# 566b4b7e-ffb1-47f2-8e62-ae72dd2330f2.net
KiCad netlist of a schematic drawn in EasyEDA
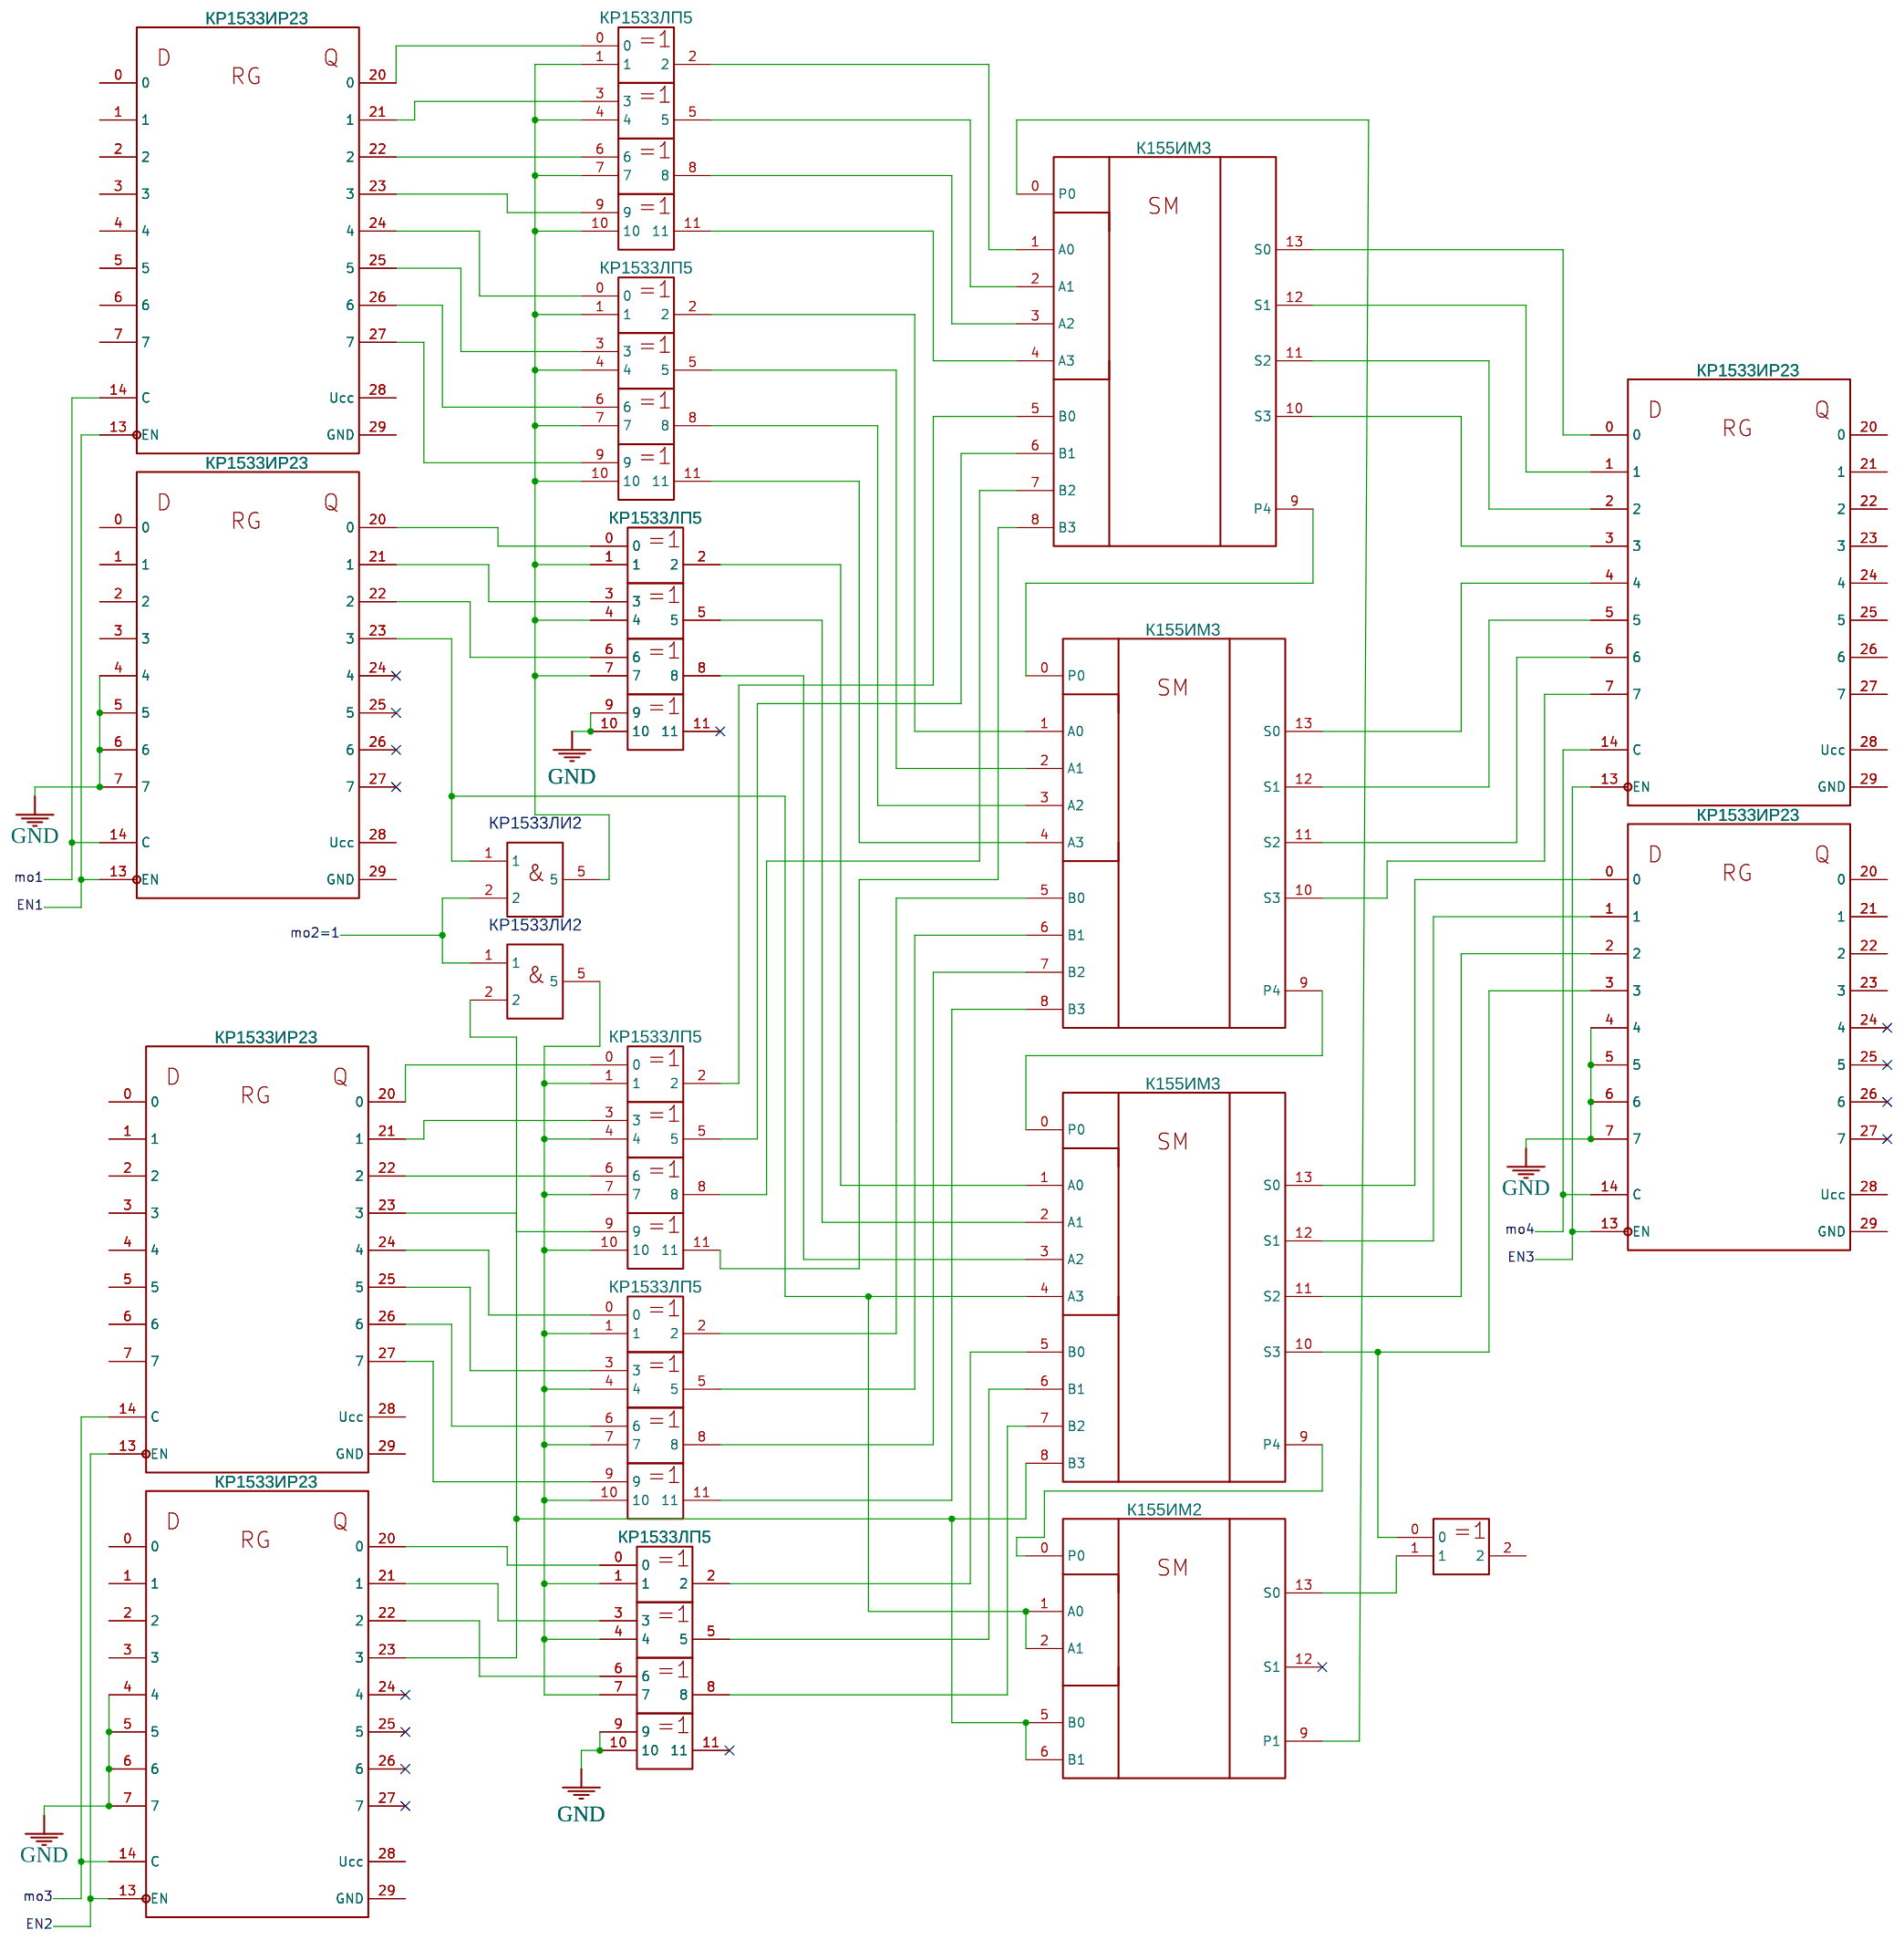
[diagram p0: schematic sheet]

(export (version "E")
  (design (tool "Eeschema 10.0.6"))
  (components
    (comp (ref "U1") (value "КР1533ИР23") (libsource (lib "") (part "regist_8")))
    (comp (ref "U2") (value "К155ИМ3") (libsource (lib "") (part "SM_1")))
    (comp (ref "U3") (value "and_or") (libsource (lib "") (part "and_or")))
    (comp (ref "U4") (value "КР1533ЛП5") (libsource (lib "") (part "4_xor")))
    (comp (ref "U5") (value "КР1533ЛП5") (libsource (lib "") (part "4_xor")))
    (comp (ref "U6") (value "КР1533ЛП5") (libsource (lib "") (part "4_xor")))
    (comp (ref "U7") (value "КР1533ИР23") (libsource (lib "") (part "regist_8")))
    (comp (ref "U8") (value "К155ИМ3") (libsource (lib "") (part "SM_1")))
    (comp (ref "U9") (value "КР1533ИР23") (libsource (lib "") (part "regist_8")))
    (comp (ref "U10") (value "КР1533ИР23") (libsource (lib "") (part "regist_8")))
    (comp (ref "U11") (value "КР1533ЛП5") (libsource (lib "") (part "4_xor")))
    (comp (ref "U12") (value "КР1533ЛП5") (libsource (lib "") (part "4_xor")))
    (comp (ref "U13") (value "КР1533ЛП5") (libsource (lib "") (part "4_xor")))
    (comp (ref "U14") (value "and_or") (libsource (lib "") (part "and_or")))
    (comp (ref "U15") (value "К155ИМ3") (libsource (lib "") (part "SM_1")))
    (comp (ref "U16") (value "КР1533ИР23") (libsource (lib "") (part "regist_8")))
    (comp (ref "U17") (value "КР1533ИР23") (libsource (lib "") (part "regist_8")))
    (comp (ref "U18") (value "К155ИМ2") (libsource (lib "") (part "SM")))
    (comp (ref "U19") (value "4_xor") (libsource (lib "") (part "4_xor_1")))
  )
  (nets
    (net (code "1") (name "/EN1") (class "Default")
      (node (ref "U1") (pin "13") (pinfunction "EN_13") (pintype "unspecified"))
      (node (ref "U7") (pin "13") (pinfunction "EN_13") (pintype "unspecified"))
    )
    (net (code "2") (name "/EN2") (class "Default")
      (node (ref "U10") (pin "13") (pinfunction "EN_13") (pintype "unspecified"))
      (node (ref "U9") (pin "13") (pinfunction "EN_13") (pintype "unspecified"))
    )
    (net (code "3") (name "/EN3") (class "Default")
      (node (ref "U16") (pin "13") (pinfunction "EN_13") (pintype "unspecified"))
      (node (ref "U17") (pin "13") (pinfunction "EN_13") (pintype "unspecified"))
    )
    (net (code "4") (name "/mo1") (class "Default")
      (node (ref "U1") (pin "14") (pinfunction "C_14") (pintype "unspecified"))
      (node (ref "U7") (pin "14") (pinfunction "C_14") (pintype "unspecified"))
    )
    (net (code "5") (name "/mo2=1") (class "Default")
      (node (ref "U14") (pin "1") (pinfunction "1_1") (pintype "unspecified"))
      (node (ref "U3") (pin "2") (pinfunction "2_2") (pintype "unspecified"))
    )
    (net (code "6") (name "/mo3") (class "Default")
      (node (ref "U10") (pin "14") (pinfunction "C_14") (pintype "unspecified"))
      (node (ref "U9") (pin "14") (pinfunction "C_14") (pintype "unspecified"))
    )
    (net (code "7") (name "/mo4") (class "Default")
      (node (ref "U16") (pin "14") (pinfunction "C_14") (pintype "unspecified"))
      (node (ref "U17") (pin "14") (pinfunction "C_14") (pintype "unspecified"))
    )
    (net (code "8") (name "GND") (class "Default")
      (node (ref "U1") (pin "4") (pinfunction "4_4") (pintype "unspecified"))
      (node (ref "U1") (pin "5") (pinfunction "5_5") (pintype "unspecified"))
      (node (ref "U1") (pin "6") (pinfunction "6_6") (pintype "unspecified"))
      (node (ref "U1") (pin "7") (pinfunction "7_7") (pintype "unspecified"))
      (node (ref "U11") (pin "10") (pinfunction "10_10") (pintype "unspecified"))
      (node (ref "U11") (pin "9") (pinfunction "9_9") (pintype "unspecified"))
      (node (ref "U16") (pin "4") (pinfunction "4_4") (pintype "unspecified"))
      (node (ref "U16") (pin "5") (pinfunction "5_5") (pintype "unspecified"))
      (node (ref "U16") (pin "6") (pinfunction "6_6") (pintype "unspecified"))
      (node (ref "U16") (pin "7") (pinfunction "7_7") (pintype "unspecified"))
      (node (ref "U6") (pin "10") (pinfunction "10_10") (pintype "unspecified"))
      (node (ref "U6") (pin "9") (pinfunction "9_9") (pintype "unspecified"))
      (node (ref "U9") (pin "4") (pinfunction "4_4") (pintype "unspecified"))
      (node (ref "U9") (pin "5") (pinfunction "5_5") (pintype "unspecified"))
      (node (ref "U9") (pin "6") (pinfunction "6_6") (pintype "unspecified"))
      (node (ref "U9") (pin "7") (pinfunction "7_7") (pintype "unspecified"))
    )
    (net (code "9") (name "Net-(U1-0-Pad20)") (class "Default")
      (node (ref "U1") (pin "20") (pinfunction "0_20") (pintype "unspecified"))
      (node (ref "U6") (pin "0") (pinfunction "0_0") (pintype "unspecified"))
    )
    (net (code "10") (name "Net-(U1-1-Pad21)") (class "Default")
      (node (ref "U1") (pin "21") (pinfunction "1_21") (pintype "unspecified"))
      (node (ref "U6") (pin "3") (pinfunction "3_3") (pintype "unspecified"))
    )
    (net (code "11") (name "Net-(U1-2-Pad22)") (class "Default")
      (node (ref "U1") (pin "22") (pinfunction "2_22") (pintype "unspecified"))
      (node (ref "U6") (pin "6") (pinfunction "6_6") (pintype "unspecified"))
    )
    (net (code "12") (name "Net-(U2-A0)") (class "Default")
      (node (ref "U2") (pin "1") (pinfunction "A0_1") (pintype "unspecified"))
      (node (ref "U4") (pin "2") (pinfunction "2_2") (pintype "unspecified"))
    )
    (net (code "13") (name "Net-(U2-A1)") (class "Default")
      (node (ref "U2") (pin "2") (pinfunction "A1_2") (pintype "unspecified"))
      (node (ref "U4") (pin "5") (pinfunction "5_5") (pintype "unspecified"))
    )
    (net (code "14") (name "Net-(U2-A2)") (class "Default")
      (node (ref "U2") (pin "3") (pinfunction "A2_3") (pintype "unspecified"))
      (node (ref "U4") (pin "8") (pinfunction "8_8") (pintype "unspecified"))
    )
    (net (code "15") (name "Net-(U2-A3)") (class "Default")
      (node (ref "U2") (pin "4") (pinfunction "A3_4") (pintype "unspecified"))
      (node (ref "U4") (pin "11") (pinfunction "11_11") (pintype "unspecified"))
    )
    (net (code "16") (name "Net-(U2-B0)") (class "Default")
      (node (ref "U13") (pin "2") (pinfunction "2_2") (pintype "unspecified"))
      (node (ref "U2") (pin "5") (pinfunction "B0_5") (pintype "unspecified"))
    )
    (net (code "17") (name "Net-(U2-B1)") (class "Default")
      (node (ref "U13") (pin "5") (pinfunction "5_5") (pintype "unspecified"))
      (node (ref "U2") (pin "6") (pinfunction "B1_6") (pintype "unspecified"))
    )
    (net (code "18") (name "Net-(U2-B2)") (class "Default")
      (node (ref "U13") (pin "8") (pinfunction "8_8") (pintype "unspecified"))
      (node (ref "U2") (pin "7") (pinfunction "B2_7") (pintype "unspecified"))
    )
    (net (code "19") (name "Net-(U2-B3)") (class "Default")
      (node (ref "U13") (pin "11") (pinfunction "11_11") (pintype "unspecified"))
      (node (ref "U2") (pin "8") (pinfunction "B3_8") (pintype "unspecified"))
    )
    (net (code "20") (name "Net-(U2-P4)") (class "Default")
      (node (ref "U2") (pin "9") (pinfunction "P4_9") (pintype "unspecified"))
      (node (ref "U8") (pin "0") (pinfunction "P0_0") (pintype "unspecified"))
    )
    (net (code "21") (name "Net-(U2-S0)") (class "Default")
      (node (ref "U17") (pin "0") (pinfunction "0_0") (pintype "unspecified"))
      (node (ref "U2") (pin "13") (pinfunction "S0_13") (pintype "unspecified"))
    )
    (net (code "22") (name "Net-(U2-S1)") (class "Default")
      (node (ref "U17") (pin "1") (pinfunction "1_1") (pintype "unspecified"))
      (node (ref "U2") (pin "12") (pinfunction "S1_12") (pintype "unspecified"))
    )
    (net (code "23") (name "Net-(U2-S2)") (class "Default")
      (node (ref "U17") (pin "2") (pinfunction "2_2") (pintype "unspecified"))
      (node (ref "U2") (pin "11") (pinfunction "S2_11") (pintype "unspecified"))
    )
    (net (code "24") (name "Net-(U2-S3)") (class "Default")
      (node (ref "U17") (pin "3") (pinfunction "3_3") (pintype "unspecified"))
      (node (ref "U2") (pin "10") (pinfunction "S3_10") (pintype "unspecified"))
    )
    (net (code "25") (name "Net-(U3-Pad5)") (class "Default")
      (node (ref "U3") (pin "5") (pinfunction "5_5") (pintype "unspecified"))
      (node (ref "U4") (pin "1") (pinfunction "1_1") (pintype "unspecified"))
      (node (ref "U4") (pin "10") (pinfunction "10_10") (pintype "unspecified"))
      (node (ref "U4") (pin "4") (pinfunction "4_4") (pintype "unspecified"))
      (node (ref "U4") (pin "7") (pinfunction "7_7") (pintype "unspecified"))
      (node (ref "U5") (pin "1") (pinfunction "1_1") (pintype "unspecified"))
      (node (ref "U5") (pin "10") (pinfunction "10_10") (pintype "unspecified"))
      (node (ref "U5") (pin "4") (pinfunction "4_4") (pintype "unspecified"))
      (node (ref "U5") (pin "7") (pinfunction "7_7") (pintype "unspecified"))
      (node (ref "U6") (pin "1") (pinfunction "1_1") (pintype "unspecified"))
      (node (ref "U6") (pin "4") (pinfunction "4_4") (pintype "unspecified"))
      (node (ref "U6") (pin "7") (pinfunction "7_7") (pintype "unspecified"))
    )
    (net (code "26") (name "Net-(U4-Pad0)") (class "Default")
      (node (ref "U4") (pin "0") (pinfunction "0_0") (pintype "unspecified"))
      (node (ref "U7") (pin "20") (pinfunction "0_20") (pintype "unspecified"))
    )
    (net (code "27") (name "Net-(U4-Pad3)") (class "Default")
      (node (ref "U4") (pin "3") (pinfunction "3_3") (pintype "unspecified"))
      (node (ref "U7") (pin "21") (pinfunction "1_21") (pintype "unspecified"))
    )
    (net (code "28") (name "Net-(U4-Pad6)") (class "Default")
      (node (ref "U4") (pin "6") (pinfunction "6_6") (pintype "unspecified"))
      (node (ref "U7") (pin "22") (pinfunction "2_22") (pintype "unspecified"))
    )
    (net (code "29") (name "Net-(U4-Pad9)") (class "Default")
      (node (ref "U4") (pin "9") (pinfunction "9_9") (pintype "unspecified"))
      (node (ref "U7") (pin "23") (pinfunction "3_23") (pintype "unspecified"))
    )
    (net (code "30") (name "Net-(U5-Pad0)") (class "Default")
      (node (ref "U5") (pin "0") (pinfunction "0_0") (pintype "unspecified"))
      (node (ref "U7") (pin "24") (pinfunction "4_24") (pintype "unspecified"))
    )
    (net (code "31") (name "Net-(U5-Pad3)") (class "Default")
      (node (ref "U5") (pin "3") (pinfunction "3_3") (pintype "unspecified"))
      (node (ref "U7") (pin "25") (pinfunction "5_25") (pintype "unspecified"))
    )
    (net (code "32") (name "Net-(U5-Pad6)") (class "Default")
      (node (ref "U5") (pin "6") (pinfunction "6_6") (pintype "unspecified"))
      (node (ref "U7") (pin "26") (pinfunction "6_26") (pintype "unspecified"))
    )
    (net (code "33") (name "Net-(U5-Pad9)") (class "Default")
      (node (ref "U5") (pin "9") (pinfunction "9_9") (pintype "unspecified"))
      (node (ref "U7") (pin "27") (pinfunction "7_27") (pintype "unspecified"))
    )
    (net (code "34") (name "Net-(U8-A0)") (class "Default")
      (node (ref "U5") (pin "2") (pinfunction "2_2") (pintype "unspecified"))
      (node (ref "U8") (pin "1") (pinfunction "A0_1") (pintype "unspecified"))
    )
    (net (code "35") (name "Net-(U8-A1)") (class "Default")
      (node (ref "U5") (pin "5") (pinfunction "5_5") (pintype "unspecified"))
      (node (ref "U8") (pin "2") (pinfunction "A1_2") (pintype "unspecified"))
    )
    (net (code "36") (name "Net-(U8-A2)") (class "Default")
      (node (ref "U5") (pin "8") (pinfunction "8_8") (pintype "unspecified"))
      (node (ref "U8") (pin "3") (pinfunction "A2_3") (pintype "unspecified"))
    )
    (net (code "37") (name "Net-(U8-A3)") (class "Default")
      (node (ref "U5") (pin "11") (pinfunction "11_11") (pintype "unspecified"))
      (node (ref "U8") (pin "4") (pinfunction "A3_4") (pintype "unspecified"))
    )
    (net (code "38") (name "Net-(U8-B0)") (class "Default")
      (node (ref "U12") (pin "2") (pinfunction "2_2") (pintype "unspecified"))
      (node (ref "U8") (pin "5") (pinfunction "B0_5") (pintype "unspecified"))
    )
    (net (code "39") (name "Net-(U8-B1)") (class "Default")
      (node (ref "U12") (pin "5") (pinfunction "5_5") (pintype "unspecified"))
      (node (ref "U8") (pin "6") (pinfunction "B1_6") (pintype "unspecified"))
    )
    (net (code "40") (name "Net-(U8-B2)") (class "Default")
      (node (ref "U12") (pin "8") (pinfunction "8_8") (pintype "unspecified"))
      (node (ref "U8") (pin "7") (pinfunction "B2_7") (pintype "unspecified"))
    )
    (net (code "41") (name "Net-(U8-B3)") (class "Default")
      (node (ref "U12") (pin "11") (pinfunction "11_11") (pintype "unspecified"))
      (node (ref "U8") (pin "8") (pinfunction "B3_8") (pintype "unspecified"))
    )
    (net (code "42") (name "Net-(U8-S0)") (class "Default")
      (node (ref "U17") (pin "4") (pinfunction "4_4") (pintype "unspecified"))
      (node (ref "U8") (pin "13") (pinfunction "S0_13") (pintype "unspecified"))
    )
    (net (code "43") (name "Net-(U8-S1)") (class "Default")
      (node (ref "U17") (pin "5") (pinfunction "5_5") (pintype "unspecified"))
      (node (ref "U8") (pin "12") (pinfunction "S1_12") (pintype "unspecified"))
    )
    (net (code "44") (name "Net-(U8-S2)") (class "Default")
      (node (ref "U17") (pin "6") (pinfunction "6_6") (pintype "unspecified"))
      (node (ref "U8") (pin "11") (pinfunction "S2_11") (pintype "unspecified"))
    )
    (net (code "45") (name "Net-(U8-S3)") (class "Default")
      (node (ref "U17") (pin "7") (pinfunction "7_7") (pintype "unspecified"))
      (node (ref "U8") (pin "10") (pinfunction "S3_10") (pintype "unspecified"))
    )
    (net (code "46") (name "Net-(U10-0-Pad20)") (class "Default")
      (node (ref "U10") (pin "20") (pinfunction "0_20") (pintype "unspecified"))
      (node (ref "U13") (pin "0") (pinfunction "0_0") (pintype "unspecified"))
    )
    (net (code "47") (name "Net-(U10-1-Pad21)") (class "Default")
      (node (ref "U10") (pin "21") (pinfunction "1_21") (pintype "unspecified"))
      (node (ref "U13") (pin "3") (pinfunction "3_3") (pintype "unspecified"))
    )
    (net (code "48") (name "Net-(U10-2-Pad22)") (class "Default")
      (node (ref "U10") (pin "22") (pinfunction "2_22") (pintype "unspecified"))
      (node (ref "U13") (pin "6") (pinfunction "6_6") (pintype "unspecified"))
    )
    (net (code "49") (name "Net-(U10-3-Pad23)") (class "Default")
      (node (ref "U10") (pin "23") (pinfunction "3_23") (pintype "unspecified"))
      (node (ref "U13") (pin "9") (pinfunction "9_9") (pintype "unspecified"))
    )
    (net (code "50") (name "Net-(U10-4-Pad24)") (class "Default")
      (node (ref "U10") (pin "24") (pinfunction "4_24") (pintype "unspecified"))
      (node (ref "U12") (pin "0") (pinfunction "0_0") (pintype "unspecified"))
    )
    (net (code "51") (name "Net-(U10-5-Pad25)") (class "Default")
      (node (ref "U10") (pin "25") (pinfunction "5_25") (pintype "unspecified"))
      (node (ref "U12") (pin "3") (pinfunction "3_3") (pintype "unspecified"))
    )
    (net (code "52") (name "Net-(U10-6-Pad26)") (class "Default")
      (node (ref "U10") (pin "26") (pinfunction "6_26") (pintype "unspecified"))
      (node (ref "U12") (pin "6") (pinfunction "6_6") (pintype "unspecified"))
    )
    (net (code "53") (name "Net-(U10-7-Pad27)") (class "Default")
      (node (ref "U10") (pin "27") (pinfunction "7_27") (pintype "unspecified"))
      (node (ref "U12") (pin "9") (pinfunction "9_9") (pintype "unspecified"))
    )
    (net (code "54") (name "Net-(U11-Pad0)") (class "Default")
      (node (ref "U11") (pin "0") (pinfunction "0_0") (pintype "unspecified"))
      (node (ref "U9") (pin "20") (pinfunction "0_20") (pintype "unspecified"))
    )
    (net (code "55") (name "Net-(U11-Pad1)") (class "Default")
      (node (ref "U11") (pin "1") (pinfunction "1_1") (pintype "unspecified"))
      (node (ref "U11") (pin "4") (pinfunction "4_4") (pintype "unspecified"))
      (node (ref "U11") (pin "7") (pinfunction "7_7") (pintype "unspecified"))
      (node (ref "U12") (pin "1") (pinfunction "1_1") (pintype "unspecified"))
      (node (ref "U12") (pin "10") (pinfunction "10_10") (pintype "unspecified"))
      (node (ref "U12") (pin "4") (pinfunction "4_4") (pintype "unspecified"))
      (node (ref "U12") (pin "7") (pinfunction "7_7") (pintype "unspecified"))
      (node (ref "U13") (pin "1") (pinfunction "1_1") (pintype "unspecified"))
      (node (ref "U13") (pin "10") (pinfunction "10_10") (pintype "unspecified"))
      (node (ref "U13") (pin "4") (pinfunction "4_4") (pintype "unspecified"))
      (node (ref "U13") (pin "7") (pinfunction "7_7") (pintype "unspecified"))
      (node (ref "U14") (pin "5") (pinfunction "5_5") (pintype "unspecified"))
    )
    (net (code "56") (name "Net-(U11-Pad3)") (class "Default")
      (node (ref "U11") (pin "3") (pinfunction "3_3") (pintype "unspecified"))
      (node (ref "U9") (pin "21") (pinfunction "1_21") (pintype "unspecified"))
    )
    (net (code "57") (name "Net-(U11-Pad6)") (class "Default")
      (node (ref "U11") (pin "6") (pinfunction "6_6") (pintype "unspecified"))
      (node (ref "U9") (pin "22") (pinfunction "2_22") (pintype "unspecified"))
    )
    (net (code "58") (name "Net-(U15-A0)") (class "Default")
      (node (ref "U15") (pin "1") (pinfunction "A0_1") (pintype "unspecified"))
      (node (ref "U6") (pin "2") (pinfunction "2_2") (pintype "unspecified"))
    )
    (net (code "59") (name "Net-(U15-A1)") (class "Default")
      (node (ref "U15") (pin "2") (pinfunction "A1_2") (pintype "unspecified"))
      (node (ref "U6") (pin "5") (pinfunction "5_5") (pintype "unspecified"))
    )
    (net (code "60") (name "Net-(U15-A2)") (class "Default")
      (node (ref "U15") (pin "3") (pinfunction "A2_3") (pintype "unspecified"))
      (node (ref "U6") (pin "8") (pinfunction "8_8") (pintype "unspecified"))
    )
    (net (code "61") (name "Net-(U15-A3)") (class "Default")
      (node (ref "U1") (pin "23") (pinfunction "3_23") (pintype "unspecified"))
      (node (ref "U15") (pin "4") (pinfunction "A3_4") (pintype "unspecified"))
      (node (ref "U18") (pin "1") (pinfunction "A0_1") (pintype "unspecified"))
      (node (ref "U18") (pin "2") (pinfunction "A1_2") (pintype "unspecified"))
      (node (ref "U3") (pin "1") (pinfunction "1_1") (pintype "unspecified"))
    )
    (net (code "62") (name "Net-(U15-B0)") (class "Default")
      (node (ref "U11") (pin "2") (pinfunction "2_2") (pintype "unspecified"))
      (node (ref "U15") (pin "5") (pinfunction "B0_5") (pintype "unspecified"))
    )
    (net (code "63") (name "Net-(U15-B1)") (class "Default")
      (node (ref "U11") (pin "5") (pinfunction "5_5") (pintype "unspecified"))
      (node (ref "U15") (pin "6") (pinfunction "B1_6") (pintype "unspecified"))
    )
    (net (code "64") (name "Net-(U15-B2)") (class "Default")
      (node (ref "U11") (pin "8") (pinfunction "8_8") (pintype "unspecified"))
      (node (ref "U15") (pin "7") (pinfunction "B2_7") (pintype "unspecified"))
    )
    (net (code "65") (name "Net-(U15-B3)") (class "Default")
      (node (ref "U14") (pin "2") (pinfunction "2_2") (pintype "unspecified"))
      (node (ref "U15") (pin "8") (pinfunction "B3_8") (pintype "unspecified"))
      (node (ref "U18") (pin "5") (pinfunction "B0_5") (pintype "unspecified"))
      (node (ref "U18") (pin "6") (pinfunction "B1_6") (pintype "unspecified"))
      (node (ref "U9") (pin "23") (pinfunction "3_23") (pintype "unspecified"))
    )
    (net (code "66") (name "Net-(U15-P0)") (class "Default")
      (node (ref "U15") (pin "0") (pinfunction "P0_0") (pintype "unspecified"))
      (node (ref "U8") (pin "9") (pinfunction "P4_9") (pintype "unspecified"))
    )
    (net (code "67") (name "Net-(U15-P4)") (class "Default")
      (node (ref "U15") (pin "9") (pinfunction "P4_9") (pintype "unspecified"))
      (node (ref "U18") (pin "0") (pinfunction "P0_0") (pintype "unspecified"))
    )
    (net (code "68") (name "Net-(U15-S0)") (class "Default")
      (node (ref "U15") (pin "13") (pinfunction "S0_13") (pintype "unspecified"))
      (node (ref "U16") (pin "0") (pinfunction "0_0") (pintype "unspecified"))
    )
    (net (code "69") (name "Net-(U15-S1)") (class "Default")
      (node (ref "U15") (pin "12") (pinfunction "S1_12") (pintype "unspecified"))
      (node (ref "U16") (pin "1") (pinfunction "1_1") (pintype "unspecified"))
    )
    (net (code "70") (name "Net-(U15-S2)") (class "Default")
      (node (ref "U15") (pin "11") (pinfunction "S2_11") (pintype "unspecified"))
      (node (ref "U16") (pin "2") (pinfunction "2_2") (pintype "unspecified"))
    )
    (net (code "71") (name "Net-(U15-S3)") (class "Default")
      (node (ref "U15") (pin "10") (pinfunction "S3_10") (pintype "unspecified"))
      (node (ref "U16") (pin "3") (pinfunction "3_3") (pintype "unspecified"))
      (node (ref "U19") (pin "0") (pinfunction "0_0") (pintype "unspecified"))
    )
    (net (code "72") (name "Net-(U18-P1)") (class "Default")
      (node (ref "U18") (pin "9") (pinfunction "P1_9") (pintype "unspecified"))
      (node (ref "U2") (pin "0") (pinfunction "P0_0") (pintype "unspecified"))
    )
    (net (code "73") (name "Net-(U18-S0)") (class "Default")
      (node (ref "U18") (pin "13") (pinfunction "S0_13") (pintype "unspecified"))
      (node (ref "U19") (pin "1") (pinfunction "1_1") (pintype "unspecified"))
    )
    (net (code "74") (name "unconnected-(U1-4-Pad24)") (class "Default")
      (node (ref "U1") (pin "24") (pinfunction "4_24") (pintype "unspecified+no_connect"))
    )
    (net (code "75") (name "unconnected-(U1-5-Pad25)") (class "Default")
      (node (ref "U1") (pin "25") (pinfunction "5_25") (pintype "unspecified+no_connect"))
    )
    (net (code "76") (name "unconnected-(U1-6-Pad26)") (class "Default")
      (node (ref "U1") (pin "26") (pinfunction "6_26") (pintype "unspecified+no_connect"))
    )
    (net (code "77") (name "unconnected-(U1-7-Pad27)") (class "Default")
      (node (ref "U1") (pin "27") (pinfunction "7_27") (pintype "unspecified+no_connect"))
    )
    (net (code "78") (name "unconnected-(U1-GND-Pad29)") (class "Default")
      (node (ref "U1") (pin "29") (pinfunction "GND_29") (pintype "unspecified"))
    )
    (net (code "79") (name "unconnected-(U1-Pad0)") (class "Default")
      (node (ref "U1") (pin "0") (pinfunction "0_0") (pintype "unspecified"))
    )
    (net (code "80") (name "unconnected-(U1-Pad1)") (class "Default")
      (node (ref "U1") (pin "1") (pinfunction "1_1") (pintype "unspecified"))
    )
    (net (code "81") (name "unconnected-(U1-Pad2)") (class "Default")
      (node (ref "U1") (pin "2") (pinfunction "2_2") (pintype "unspecified"))
    )
    (net (code "82") (name "unconnected-(U1-Pad3)") (class "Default")
      (node (ref "U1") (pin "3") (pinfunction "3_3") (pintype "unspecified"))
    )
    (net (code "83") (name "unconnected-(U1-Ucc-Pad28)") (class "Default")
      (node (ref "U1") (pin "28") (pinfunction "Ucc_28") (pintype "unspecified"))
    )
    (net (code "84") (name "unconnected-(U6-Pad11)") (class "Default")
      (node (ref "U6") (pin "11") (pinfunction "11_11") (pintype "unspecified+no_connect"))
    )
    (net (code "85") (name "unconnected-(U7-GND-Pad29)") (class "Default")
      (node (ref "U7") (pin "29") (pinfunction "GND_29") (pintype "unspecified"))
    )
    (net (code "86") (name "unconnected-(U7-Pad0)") (class "Default")
      (node (ref "U7") (pin "0") (pinfunction "0_0") (pintype "unspecified"))
    )
    (net (code "87") (name "unconnected-(U7-Pad1)") (class "Default")
      (node (ref "U7") (pin "1") (pinfunction "1_1") (pintype "unspecified"))
    )
    (net (code "88") (name "unconnected-(U7-Pad2)") (class "Default")
      (node (ref "U7") (pin "2") (pinfunction "2_2") (pintype "unspecified"))
    )
    (net (code "89") (name "unconnected-(U7-Pad3)") (class "Default")
      (node (ref "U7") (pin "3") (pinfunction "3_3") (pintype "unspecified"))
    )
    (net (code "90") (name "unconnected-(U7-Pad4)") (class "Default")
      (node (ref "U7") (pin "4") (pinfunction "4_4") (pintype "unspecified"))
    )
    (net (code "91") (name "unconnected-(U7-Pad5)") (class "Default")
      (node (ref "U7") (pin "5") (pinfunction "5_5") (pintype "unspecified"))
    )
    (net (code "92") (name "unconnected-(U7-Pad6)") (class "Default")
      (node (ref "U7") (pin "6") (pinfunction "6_6") (pintype "unspecified"))
    )
    (net (code "93") (name "unconnected-(U7-Pad7)") (class "Default")
      (node (ref "U7") (pin "7") (pinfunction "7_7") (pintype "unspecified"))
    )
    (net (code "94") (name "unconnected-(U7-Ucc-Pad28)") (class "Default")
      (node (ref "U7") (pin "28") (pinfunction "Ucc_28") (pintype "unspecified"))
    )
    (net (code "95") (name "unconnected-(U9-4-Pad24)") (class "Default")
      (node (ref "U9") (pin "24") (pinfunction "4_24") (pintype "unspecified+no_connect"))
    )
    (net (code "96") (name "unconnected-(U9-5-Pad25)") (class "Default")
      (node (ref "U9") (pin "25") (pinfunction "5_25") (pintype "unspecified+no_connect"))
    )
    (net (code "97") (name "unconnected-(U9-6-Pad26)") (class "Default")
      (node (ref "U9") (pin "26") (pinfunction "6_26") (pintype "unspecified+no_connect"))
    )
    (net (code "98") (name "unconnected-(U9-7-Pad27)") (class "Default")
      (node (ref "U9") (pin "27") (pinfunction "7_27") (pintype "unspecified+no_connect"))
    )
    (net (code "99") (name "unconnected-(U9-GND-Pad29)") (class "Default")
      (node (ref "U9") (pin "29") (pinfunction "GND_29") (pintype "unspecified"))
    )
    (net (code "100") (name "unconnected-(U9-Pad0)") (class "Default")
      (node (ref "U9") (pin "0") (pinfunction "0_0") (pintype "unspecified"))
    )
    (net (code "101") (name "unconnected-(U9-Pad1)") (class "Default")
      (node (ref "U9") (pin "1") (pinfunction "1_1") (pintype "unspecified"))
    )
    (net (code "102") (name "unconnected-(U9-Pad2)") (class "Default")
      (node (ref "U9") (pin "2") (pinfunction "2_2") (pintype "unspecified"))
    )
    (net (code "103") (name "unconnected-(U9-Pad3)") (class "Default")
      (node (ref "U9") (pin "3") (pinfunction "3_3") (pintype "unspecified"))
    )
    (net (code "104") (name "unconnected-(U9-Ucc-Pad28)") (class "Default")
      (node (ref "U9") (pin "28") (pinfunction "Ucc_28") (pintype "unspecified"))
    )
    (net (code "105") (name "unconnected-(U10-GND-Pad29)") (class "Default")
      (node (ref "U10") (pin "29") (pinfunction "GND_29") (pintype "unspecified"))
    )
    (net (code "106") (name "unconnected-(U10-Pad0)") (class "Default")
      (node (ref "U10") (pin "0") (pinfunction "0_0") (pintype "unspecified"))
    )
    (net (code "107") (name "unconnected-(U10-Pad1)") (class "Default")
      (node (ref "U10") (pin "1") (pinfunction "1_1") (pintype "unspecified"))
    )
    (net (code "108") (name "unconnected-(U10-Pad2)") (class "Default")
      (node (ref "U10") (pin "2") (pinfunction "2_2") (pintype "unspecified"))
    )
    (net (code "109") (name "unconnected-(U10-Pad3)") (class "Default")
      (node (ref "U10") (pin "3") (pinfunction "3_3") (pintype "unspecified"))
    )
    (net (code "110") (name "unconnected-(U10-Pad4)") (class "Default")
      (node (ref "U10") (pin "4") (pinfunction "4_4") (pintype "unspecified"))
    )
    (net (code "111") (name "unconnected-(U10-Pad5)") (class "Default")
      (node (ref "U10") (pin "5") (pinfunction "5_5") (pintype "unspecified"))
    )
    (net (code "112") (name "unconnected-(U10-Pad6)") (class "Default")
      (node (ref "U10") (pin "6") (pinfunction "6_6") (pintype "unspecified"))
    )
    (net (code "113") (name "unconnected-(U10-Pad7)") (class "Default")
      (node (ref "U10") (pin "7") (pinfunction "7_7") (pintype "unspecified"))
    )
    (net (code "114") (name "unconnected-(U10-Ucc-Pad28)") (class "Default")
      (node (ref "U10") (pin "28") (pinfunction "Ucc_28") (pintype "unspecified"))
    )
    (net (code "115") (name "unconnected-(U11-Pad11)") (class "Default")
      (node (ref "U11") (pin "11") (pinfunction "11_11") (pintype "unspecified+no_connect"))
    )
    (net (code "116") (name "unconnected-(U16-0-Pad20)") (class "Default")
      (node (ref "U16") (pin "20") (pinfunction "0_20") (pintype "unspecified"))
    )
    (net (code "117") (name "unconnected-(U16-1-Pad21)") (class "Default")
      (node (ref "U16") (pin "21") (pinfunction "1_21") (pintype "unspecified"))
    )
    (net (code "118") (name "unconnected-(U16-2-Pad22)") (class "Default")
      (node (ref "U16") (pin "22") (pinfunction "2_22") (pintype "unspecified"))
    )
    (net (code "119") (name "unconnected-(U16-3-Pad23)") (class "Default")
      (node (ref "U16") (pin "23") (pinfunction "3_23") (pintype "unspecified"))
    )
    (net (code "120") (name "unconnected-(U16-4-Pad24)") (class "Default")
      (node (ref "U16") (pin "24") (pinfunction "4_24") (pintype "unspecified+no_connect"))
    )
    (net (code "121") (name "unconnected-(U16-5-Pad25)") (class "Default")
      (node (ref "U16") (pin "25") (pinfunction "5_25") (pintype "unspecified+no_connect"))
    )
    (net (code "122") (name "unconnected-(U16-6-Pad26)") (class "Default")
      (node (ref "U16") (pin "26") (pinfunction "6_26") (pintype "unspecified+no_connect"))
    )
    (net (code "123") (name "unconnected-(U16-7-Pad27)") (class "Default")
      (node (ref "U16") (pin "27") (pinfunction "7_27") (pintype "unspecified+no_connect"))
    )
    (net (code "124") (name "unconnected-(U16-GND-Pad29)") (class "Default")
      (node (ref "U16") (pin "29") (pinfunction "GND_29") (pintype "unspecified"))
    )
    (net (code "125") (name "unconnected-(U16-Ucc-Pad28)") (class "Default")
      (node (ref "U16") (pin "28") (pinfunction "Ucc_28") (pintype "unspecified"))
    )
    (net (code "126") (name "unconnected-(U17-0-Pad20)") (class "Default")
      (node (ref "U17") (pin "20") (pinfunction "0_20") (pintype "unspecified"))
    )
    (net (code "127") (name "unconnected-(U17-1-Pad21)") (class "Default")
      (node (ref "U17") (pin "21") (pinfunction "1_21") (pintype "unspecified"))
    )
    (net (code "128") (name "unconnected-(U17-2-Pad22)") (class "Default")
      (node (ref "U17") (pin "22") (pinfunction "2_22") (pintype "unspecified"))
    )
    (net (code "129") (name "unconnected-(U17-3-Pad23)") (class "Default")
      (node (ref "U17") (pin "23") (pinfunction "3_23") (pintype "unspecified"))
    )
    (net (code "130") (name "unconnected-(U17-4-Pad24)") (class "Default")
      (node (ref "U17") (pin "24") (pinfunction "4_24") (pintype "unspecified"))
    )
    (net (code "131") (name "unconnected-(U17-5-Pad25)") (class "Default")
      (node (ref "U17") (pin "25") (pinfunction "5_25") (pintype "unspecified"))
    )
    (net (code "132") (name "unconnected-(U17-6-Pad26)") (class "Default")
      (node (ref "U17") (pin "26") (pinfunction "6_26") (pintype "unspecified"))
    )
    (net (code "133") (name "unconnected-(U17-7-Pad27)") (class "Default")
      (node (ref "U17") (pin "27") (pinfunction "7_27") (pintype "unspecified"))
    )
    (net (code "134") (name "unconnected-(U17-GND-Pad29)") (class "Default")
      (node (ref "U17") (pin "29") (pinfunction "GND_29") (pintype "unspecified"))
    )
    (net (code "135") (name "unconnected-(U17-Ucc-Pad28)") (class "Default")
      (node (ref "U17") (pin "28") (pinfunction "Ucc_28") (pintype "unspecified"))
    )
    (net (code "136") (name "unconnected-(U18-S1-Pad12)") (class "Default")
      (node (ref "U18") (pin "12") (pinfunction "S1_12") (pintype "unspecified+no_connect"))
    )
    (net (code "137") (name "unconnected-(U19-Pad2)") (class "Default")
      (node (ref "U19") (pin "2") (pinfunction "2_2") (pintype "unspecified"))
    )
  )
)
